# bird_beaks_3_0.net
KiCad netlist of a schematic drawn in EAGLE
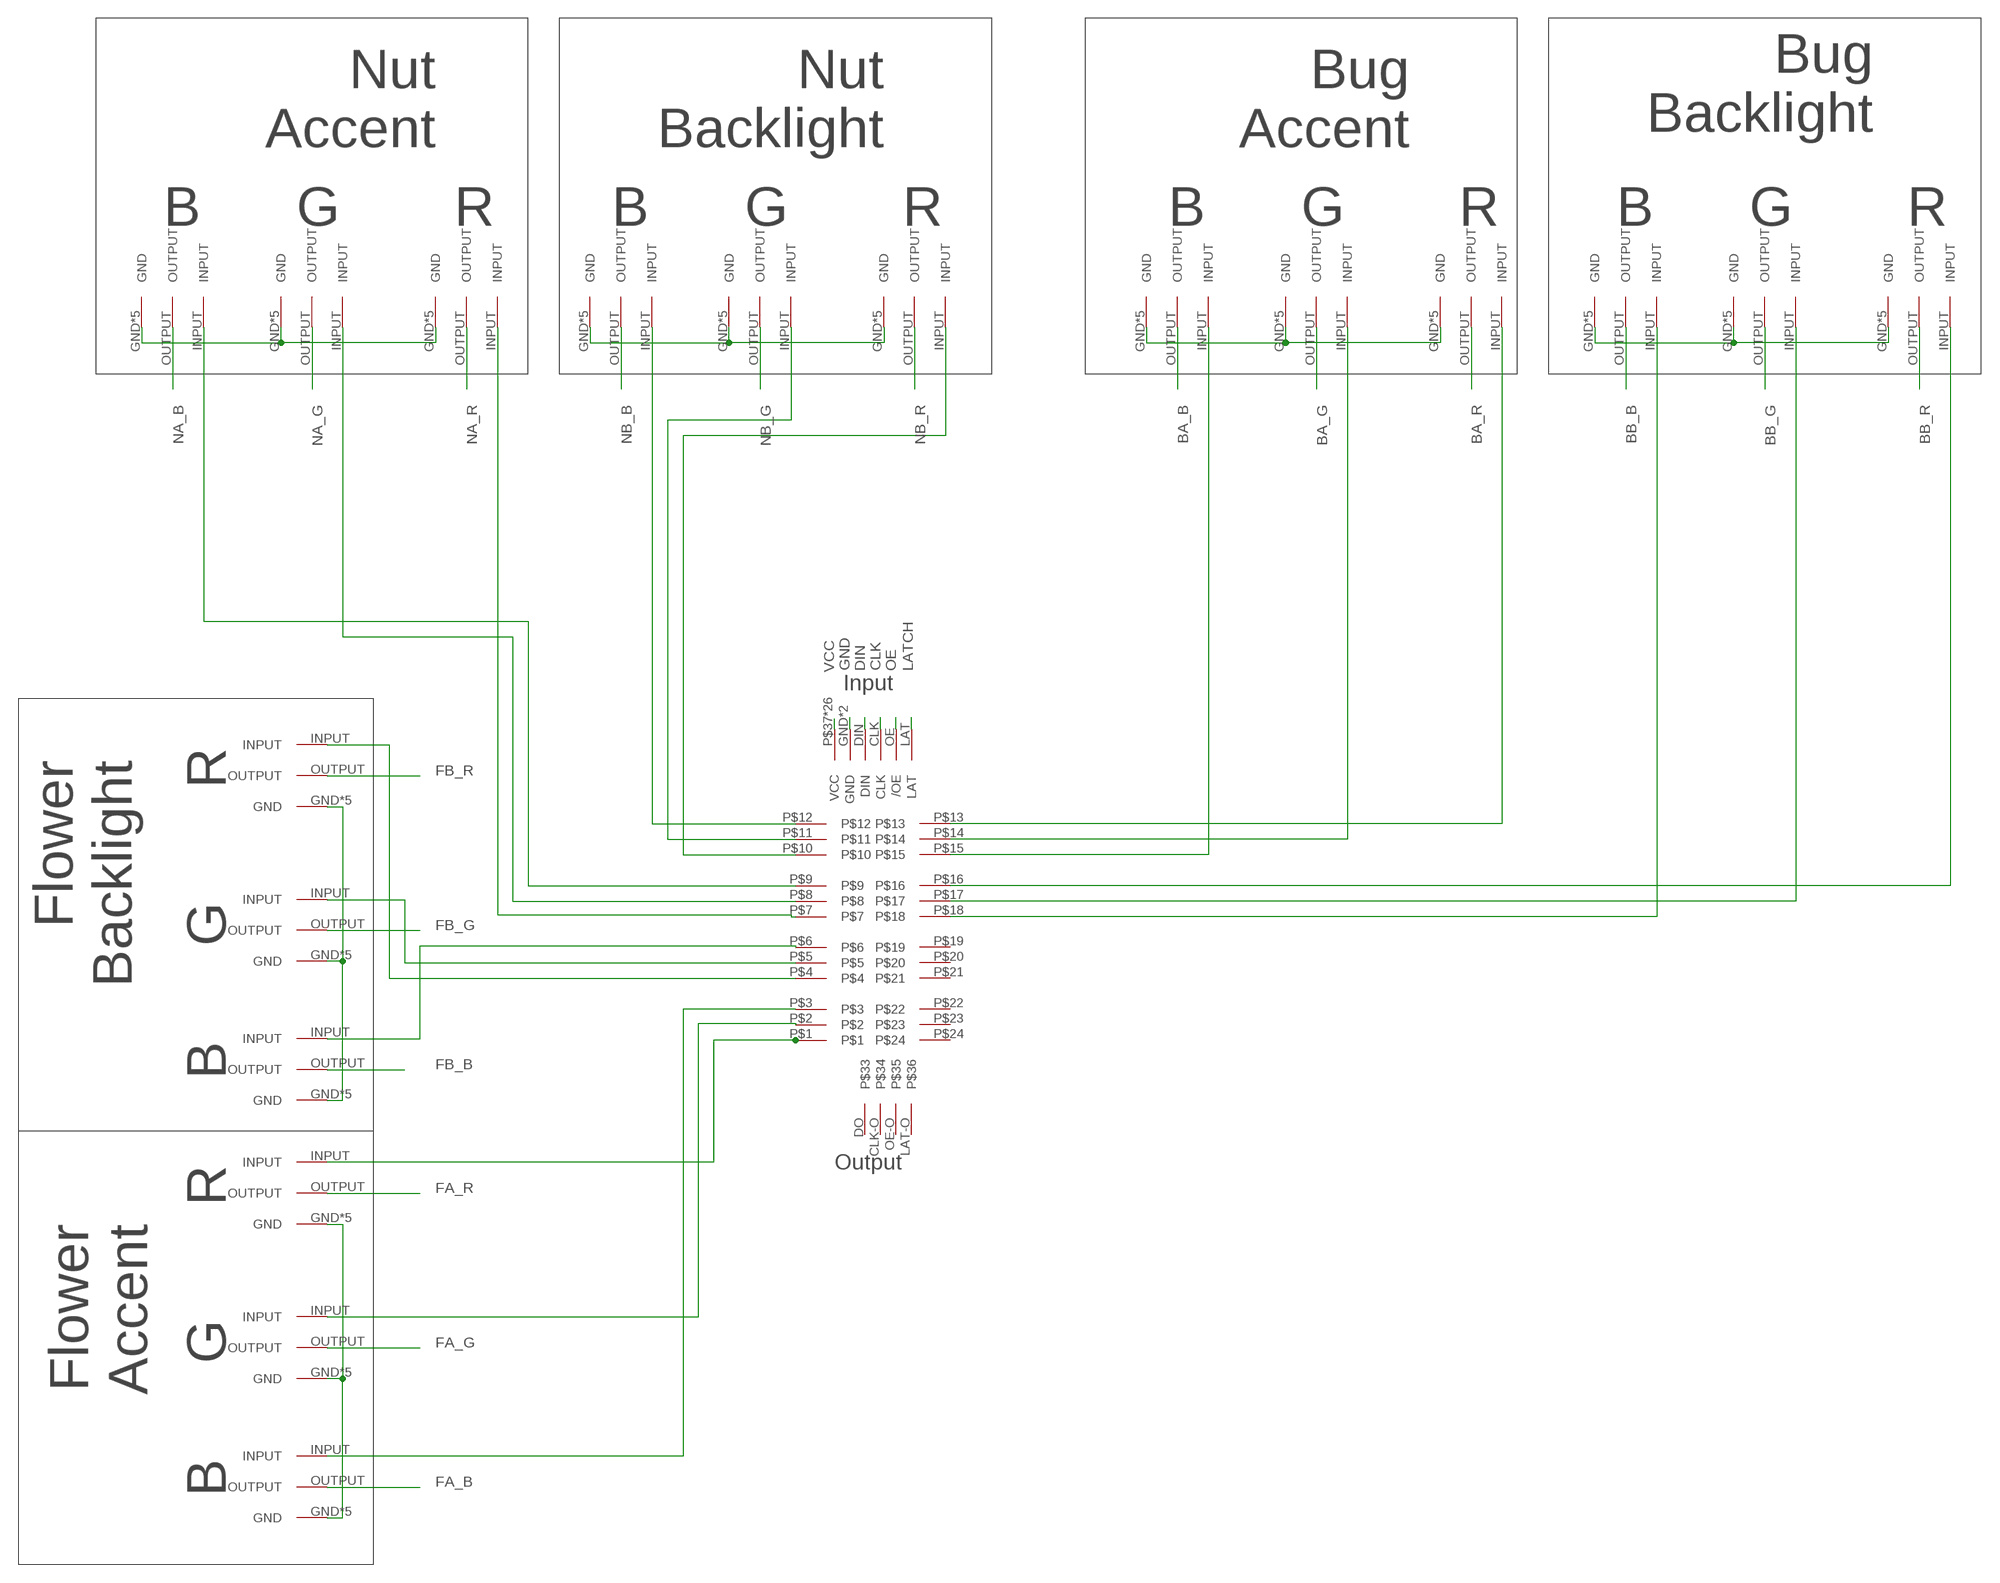
[diagram p0: schematic, sheet 1]
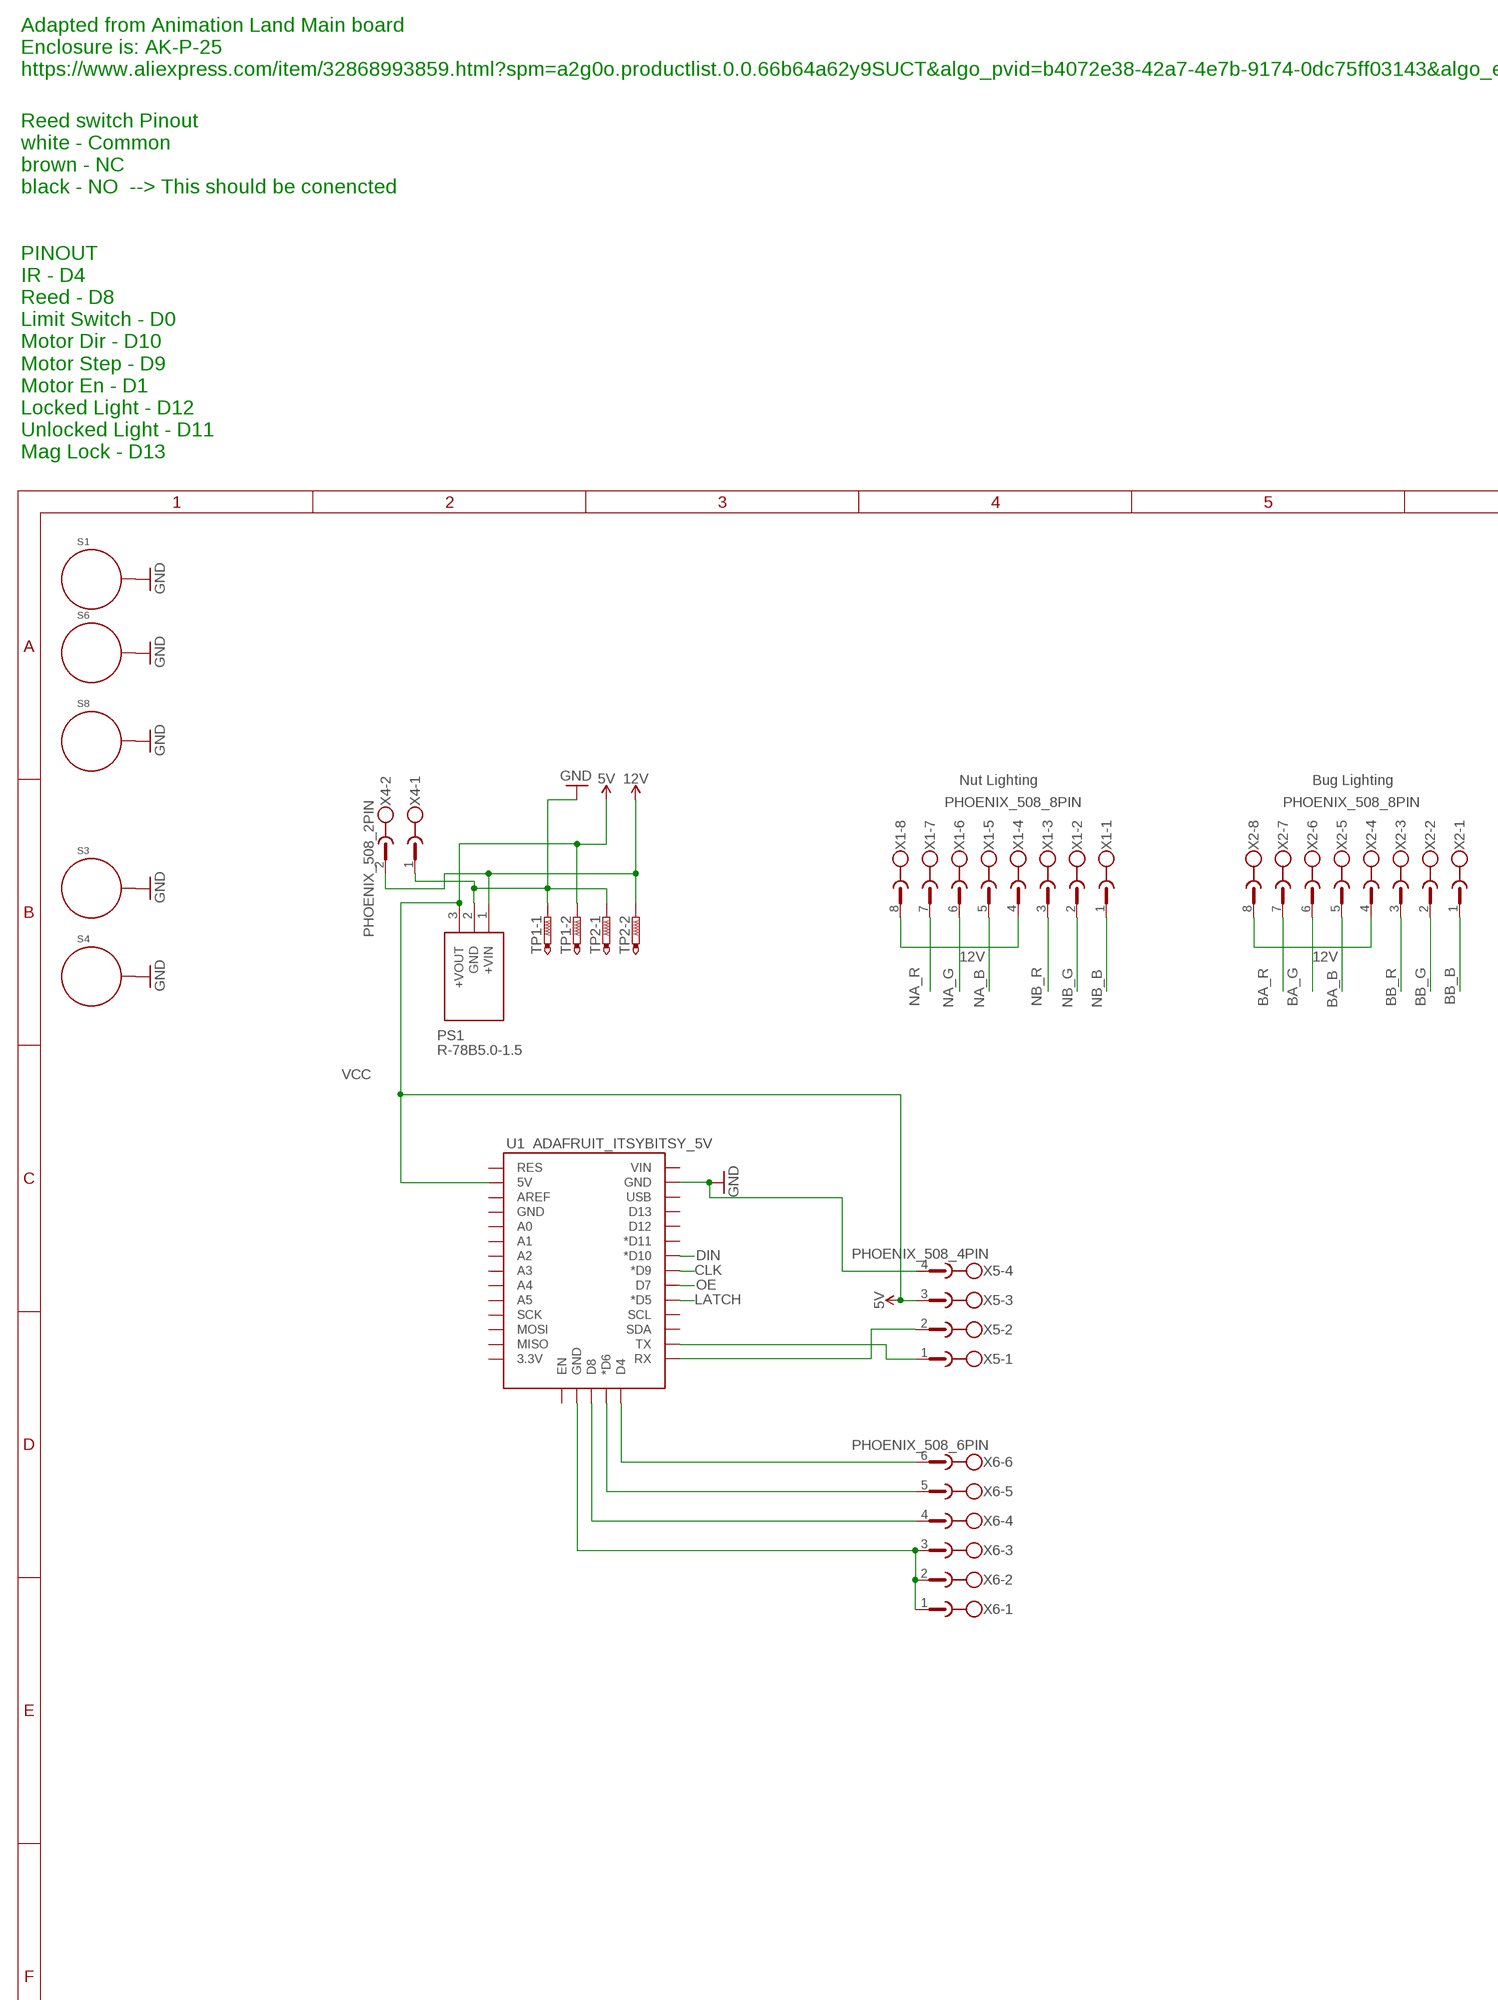
[diagram p1: schematic, sheet 2, part 1 of 2]
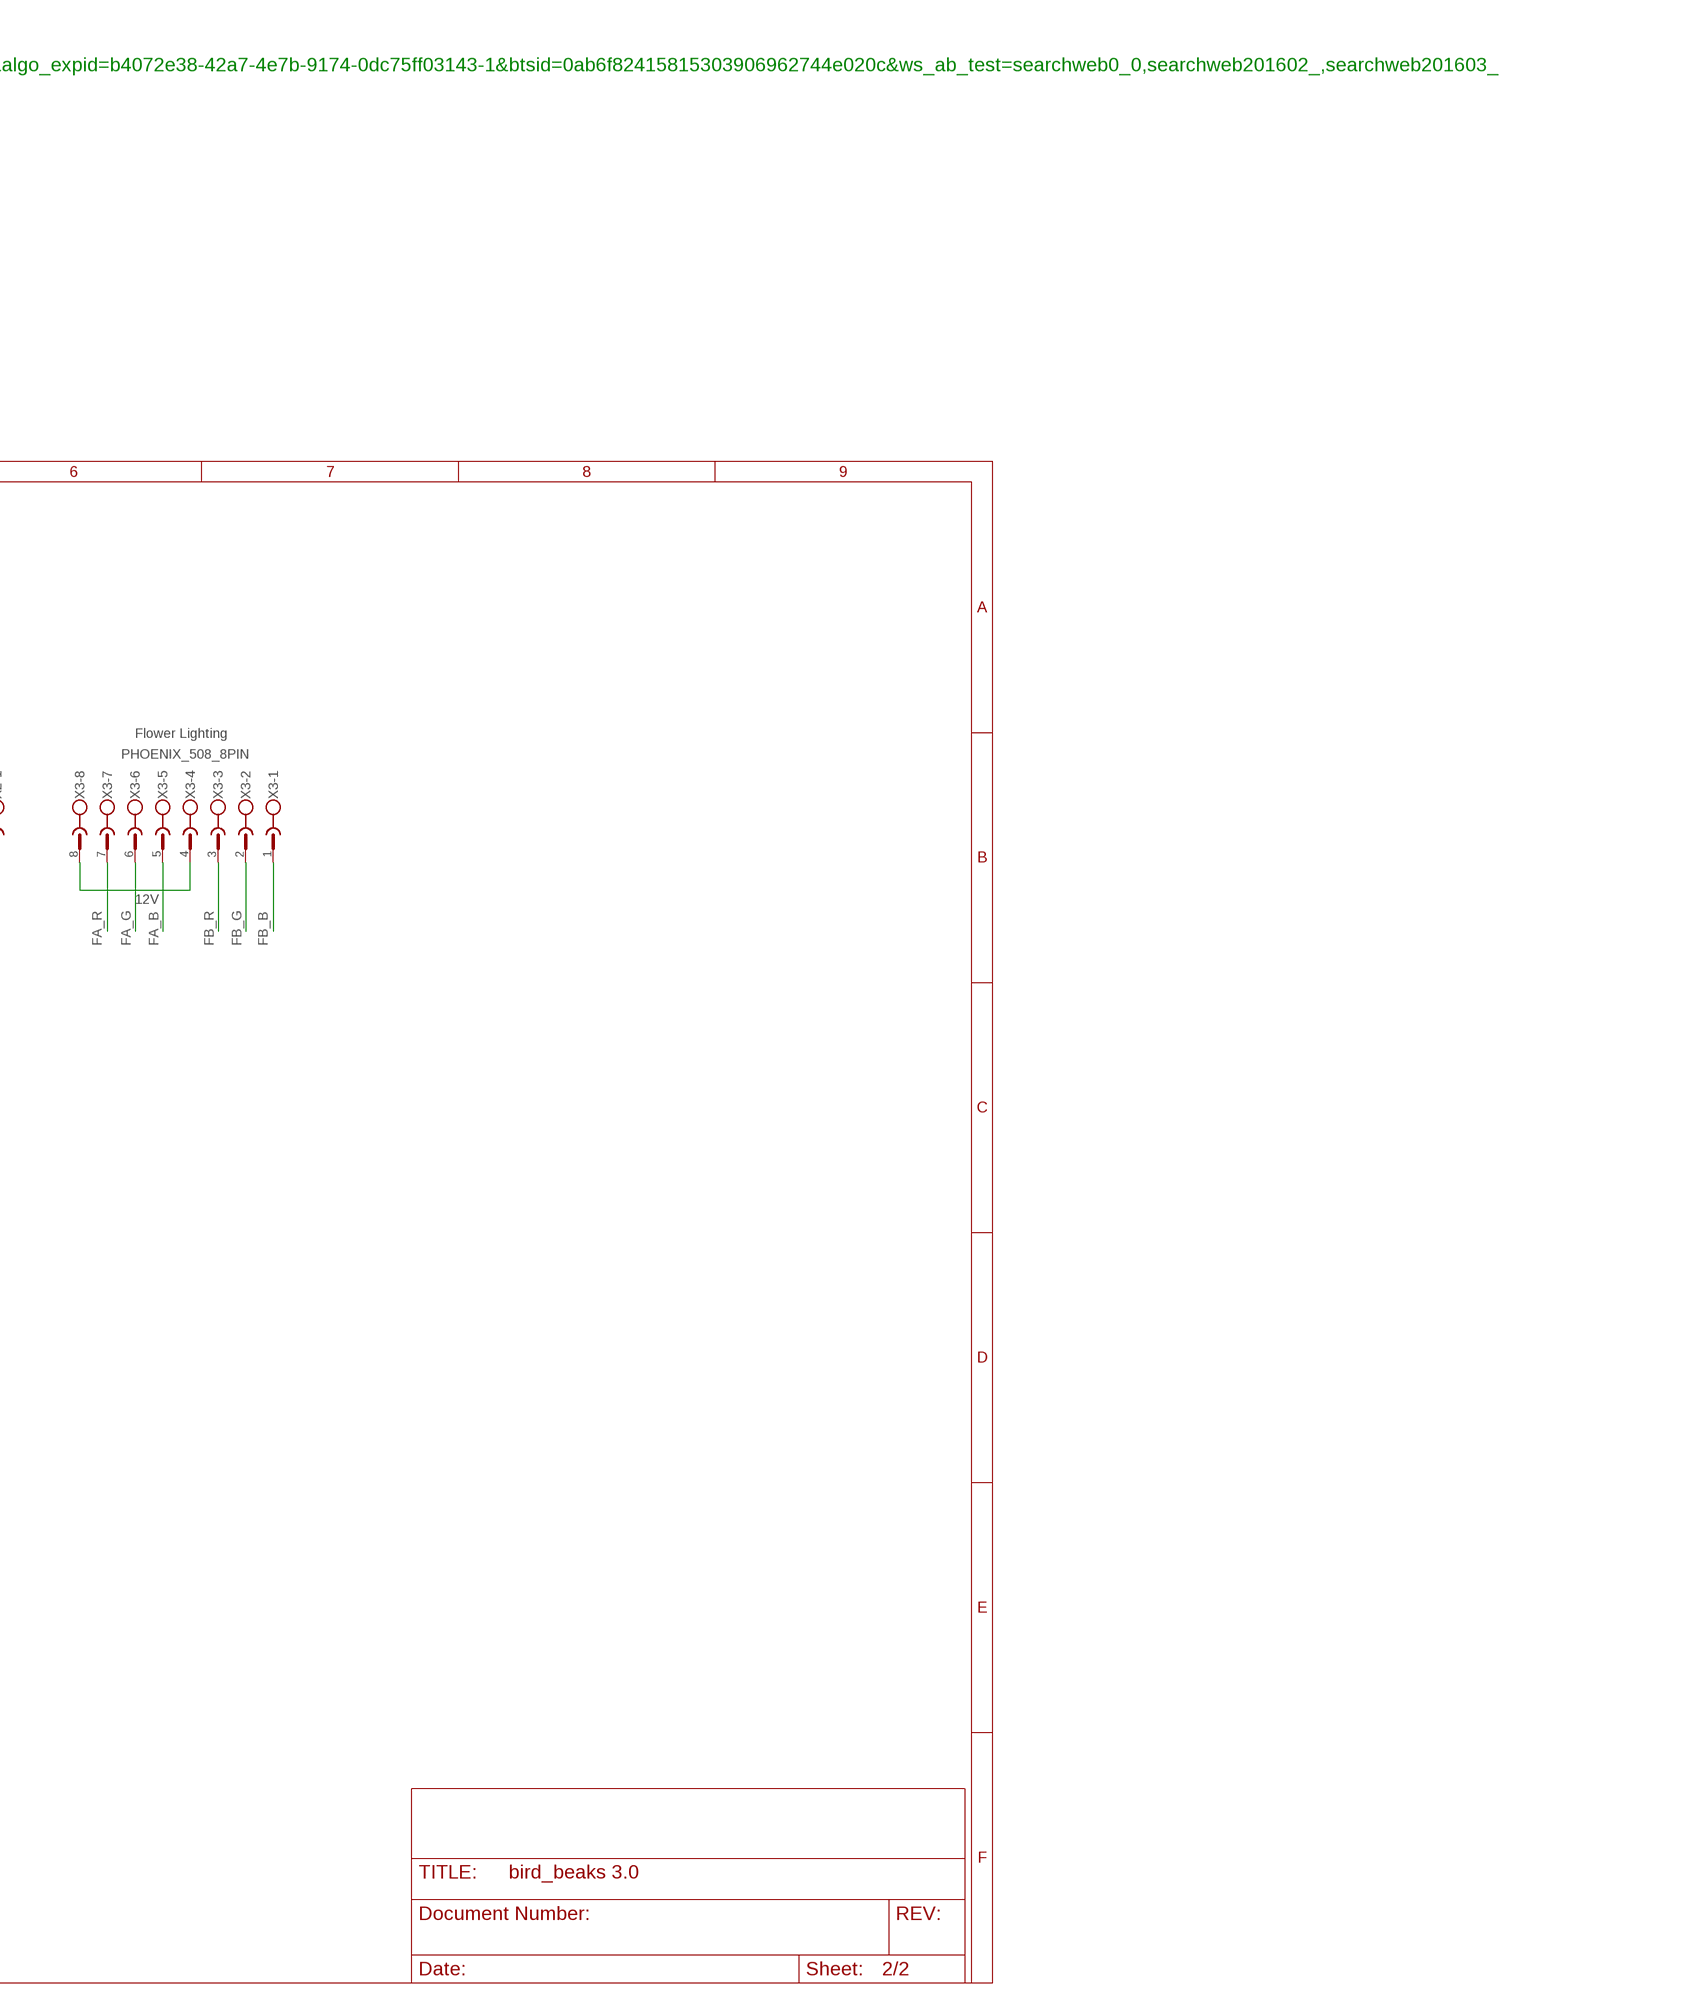
[diagram p2: schematic, sheet 2, part 2 of 2]

(export (version "E")
  (design (tool "Eeschema 10.0.6"))
  (components
    (comp (ref "PS1")
      (value "R-78B5.0-1.5")
      (footprint "eagle-import:R78B5015")
      (fields (field (name "MOUSER_PART_NUMBER") "919-R-78B5.0-1.5"))
      (libsource (lib "eagle-import") (part "R-78B5.0-1.5"))
    )
    (comp (ref "S1")
      (value "STANDOFF_ELECTRICAL5-32")
      (footprint "eagle-import:STANDOFF_ELECTRICAL_5_32")
      (libsource (lib "eagle-import") (part "STANDOFF_ELECTRICAL5-32"))
    )
    (comp (ref "S3")
      (value "STANDOFF_ELECTRICAL5-32")
      (footprint "eagle-import:STANDOFF_ELECTRICAL_5_32")
      (libsource (lib "eagle-import") (part "STANDOFF_ELECTRICAL5-32"))
    )
    (comp (ref "S4")
      (value "STANDOFF_ELECTRICAL5-32")
      (footprint "eagle-import:STANDOFF_ELECTRICAL_5_32")
      (libsource (lib "eagle-import") (part "STANDOFF_ELECTRICAL5-32"))
    )
    (comp (ref "S6")
      (value "STANDOFF_ELECTRICAL5-32")
      (footprint "eagle-import:STANDOFF_ELECTRICAL_5_32")
      (libsource (lib "eagle-import") (part "STANDOFF_ELECTRICAL5-32"))
    )
    (comp (ref "S8")
      (value "STANDOFF_ELECTRICAL5-32")
      (footprint "eagle-import:STANDOFF_ELECTRICAL_5_32")
      (libsource (lib "eagle-import") (part "STANDOFF_ELECTRICAL5-32"))
    )
    (comp (ref "TP1")
      (value "PTR2")
      (footprint "eagle-import:P2-38-17")
      (libsource (lib "eagle-import") (part "PTR2"))
    )
    (comp (ref "TP2")
      (value "PTR2")
      (footprint "eagle-import:P2-38-17")
      (libsource (lib "eagle-import") (part "PTR2"))
    )
    (comp (ref "U1")
      (value "ADAFRUIT_ITSYBITSY_5V")
      (footprint "eagle-import:ADAFRUIT_ITSYBITSY")
      (libsource (lib "eagle-import") (part "ADAFRUIT_ITSYBITSY_5V"))
    )
    (comp (ref "X1")
      (value "PHOENIX_508_8PIN")
      (footprint "eagle-import:PHOENIX_508_8PIN")
      (fields (field (name "MF") "FARNELL") (field (name "MPN") "1757307"))
      (libsource (lib "eagle-import") (part "PHOENIX_508_8PIN"))
    )
    (comp (ref "X2")
      (value "PHOENIX_508_8PIN")
      (footprint "eagle-import:PHOENIX_508_8PIN")
      (fields (field (name "MF") "FARNELL") (field (name "MPN") "1757307"))
      (libsource (lib "eagle-import") (part "PHOENIX_508_8PIN"))
    )
    (comp (ref "X3")
      (value "PHOENIX_508_8PIN")
      (footprint "eagle-import:PHOENIX_508_8PIN")
      (fields (field (name "MF") "FARNELL") (field (name "MPN") "1757307"))
      (libsource (lib "eagle-import") (part "PHOENIX_508_8PIN"))
    )
    (comp (ref "X4")
      (value "PHOENIX_508_2PIN")
      (footprint "eagle-import:PHOENIX_508_2PIN")
      (fields (field (name "MF") "FARNELL") (field (name "MPN") "1757242"))
      (libsource (lib "eagle-import") (part "PHOENIX_508_2PIN"))
    )
    (comp (ref "X5")
      (value "PHOENIX_508_4PIN")
      (footprint "eagle-import:PHOENIX_508_4PIN")
      (fields (field (name "MF") "FARNELL") (field (name "MPN") "1757268"))
      (libsource (lib "eagle-import") (part "PHOENIX_508_4PIN"))
    )
    (comp (ref "X6")
      (value "PHOENIX_508_6PIN")
      (footprint "eagle-import:PHOENIX_508_6PIN")
      (fields (field (name "MF") "FARNELL") (field (name "MPN") "1757284"))
      (libsource (lib "eagle-import") (part "PHOENIX_508_6PIN"))
    )
    (comp (ref "U$1")
      (value "TLC5847")
      (footprint "eagle-import:TLC5947")
      (libsource (lib "eagle-import") (part "TLC5847"))
    )
    (comp (ref "U$2")
      (value "MODULE_MOSFET")
      (footprint "eagle-import:MODULE_MOSFET")
      (libsource (lib "eagle-import") (part "MODULE_MOSFET"))
    )
    (comp (ref "U$3")
      (value "MODULE_MOSFET")
      (footprint "eagle-import:MODULE_MOSFET")
      (libsource (lib "eagle-import") (part "MODULE_MOSFET"))
    )
    (comp (ref "U$4")
      (value "MODULE_MOSFET")
      (footprint "eagle-import:MODULE_MOSFET")
      (libsource (lib "eagle-import") (part "MODULE_MOSFET"))
    )
    (comp (ref "U$5")
      (value "MODULE_MOSFET")
      (footprint "eagle-import:MODULE_MOSFET")
      (libsource (lib "eagle-import") (part "MODULE_MOSFET"))
    )
    (comp (ref "U$6")
      (value "MODULE_MOSFET")
      (footprint "eagle-import:MODULE_MOSFET")
      (libsource (lib "eagle-import") (part "MODULE_MOSFET"))
    )
    (comp (ref "U$7")
      (value "MODULE_MOSFET")
      (footprint "eagle-import:MODULE_MOSFET")
      (libsource (lib "eagle-import") (part "MODULE_MOSFET"))
    )
    (comp (ref "U$8")
      (value "MODULE_MOSFET")
      (footprint "eagle-import:MODULE_MOSFET")
      (libsource (lib "eagle-import") (part "MODULE_MOSFET"))
    )
    (comp (ref "U$9")
      (value "MODULE_MOSFET")
      (footprint "eagle-import:MODULE_MOSFET")
      (libsource (lib "eagle-import") (part "MODULE_MOSFET"))
    )
    (comp (ref "U$10")
      (value "MODULE_MOSFET")
      (footprint "eagle-import:MODULE_MOSFET")
      (libsource (lib "eagle-import") (part "MODULE_MOSFET"))
    )
    (comp (ref "U$11")
      (value "MODULE_MOSFET")
      (footprint "eagle-import:MODULE_MOSFET")
      (libsource (lib "eagle-import") (part "MODULE_MOSFET"))
    )
    (comp (ref "U$12")
      (value "MODULE_MOSFET")
      (footprint "eagle-import:MODULE_MOSFET")
      (libsource (lib "eagle-import") (part "MODULE_MOSFET"))
    )
    (comp (ref "U$13")
      (value "MODULE_MOSFET")
      (footprint "eagle-import:MODULE_MOSFET")
      (libsource (lib "eagle-import") (part "MODULE_MOSFET"))
    )
    (comp (ref "U$14")
      (value "MODULE_MOSFET")
      (footprint "eagle-import:MODULE_MOSFET")
      (libsource (lib "eagle-import") (part "MODULE_MOSFET"))
    )
    (comp (ref "U$15")
      (value "MODULE_MOSFET")
      (footprint "eagle-import:MODULE_MOSFET")
      (libsource (lib "eagle-import") (part "MODULE_MOSFET"))
    )
    (comp (ref "U$16")
      (value "MODULE_MOSFET")
      (footprint "eagle-import:MODULE_MOSFET")
      (libsource (lib "eagle-import") (part "MODULE_MOSFET"))
    )
    (comp (ref "U$17")
      (value "MODULE_MOSFET")
      (footprint "eagle-import:MODULE_MOSFET")
      (libsource (lib "eagle-import") (part "MODULE_MOSFET"))
    )
    (comp (ref "U$18")
      (value "MODULE_MOSFET")
      (footprint "eagle-import:MODULE_MOSFET")
      (libsource (lib "eagle-import") (part "MODULE_MOSFET"))
    )
    (comp (ref "U$19")
      (value "MODULE_MOSFET")
      (footprint "eagle-import:MODULE_MOSFET")
      (libsource (lib "eagle-import") (part "MODULE_MOSFET"))
    )
  )
  (nets
    (net (code "1") (name "12V") (class "Default")
      (node (ref "PS1") (pin "1") (pinfunction "+VIN_1") (pintype "bidirectional"))
      (node (ref "TP2") (pin "TP-2") (pinfunction "TP_TP-2") (pintype "input"))
      (node (ref "X1") (pin "4") (pinfunction "1_4") (pintype "passive"))
      (node (ref "X1") (pin "8") (pinfunction "1_8") (pintype "passive"))
      (node (ref "X2") (pin "4") (pinfunction "1_4") (pintype "passive"))
      (node (ref "X2") (pin "8") (pinfunction "1_8") (pintype "passive"))
      (node (ref "X3") (pin "4") (pinfunction "1_4") (pintype "passive"))
      (node (ref "X3") (pin "8") (pinfunction "1_8") (pintype "passive"))
      (node (ref "X4") (pin "2") (pinfunction "1_2") (pintype "passive"))
    )
    (net (code "2") (name "BA_B") (class "Default")
      (node (ref "U$14") (pin "OUTPUT") (pinfunction "OUTPUT_OUTPUT") (pintype "bidirectional"))
      (node (ref "X2") (pin "5") (pinfunction "1_5") (pintype "passive"))
    )
    (net (code "3") (name "BA_G") (class "Default")
      (node (ref "U$16") (pin "OUTPUT") (pinfunction "OUTPUT_OUTPUT") (pintype "bidirectional"))
      (node (ref "X2") (pin "6") (pinfunction "1_6") (pintype "passive"))
    )
    (net (code "4") (name "BA_R") (class "Default")
      (node (ref "U$15") (pin "OUTPUT") (pinfunction "OUTPUT_OUTPUT") (pintype "bidirectional"))
      (node (ref "X2") (pin "7") (pinfunction "1_7") (pintype "passive"))
    )
    (net (code "5") (name "BB_B") (class "Default")
      (node (ref "U$17") (pin "OUTPUT") (pinfunction "OUTPUT_OUTPUT") (pintype "bidirectional"))
      (node (ref "X2") (pin "1") (pinfunction "1_1") (pintype "passive"))
    )
    (net (code "6") (name "BB_G") (class "Default")
      (node (ref "U$19") (pin "OUTPUT") (pinfunction "OUTPUT_OUTPUT") (pintype "bidirectional"))
      (node (ref "X2") (pin "2") (pinfunction "1_2") (pintype "passive"))
    )
    (net (code "7") (name "BB_R") (class "Default")
      (node (ref "U$18") (pin "OUTPUT") (pinfunction "OUTPUT_OUTPUT") (pintype "bidirectional"))
      (node (ref "X2") (pin "3") (pinfunction "1_3") (pintype "passive"))
    )
    (net (code "8") (name "CLK") (class "Default")
      (node (ref "U$1") (pin "CLK") (pinfunction "CLK_CLK") (pintype "bidirectional"))
      (node (ref "U1") (pin "D9") (pinfunction "*D9_D9") (pintype "bidirectional"))
    )
    (net (code "9") (name "DIN") (class "Default")
      (node (ref "U$1") (pin "DIN") (pinfunction "DIN_DIN") (pintype "bidirectional"))
      (node (ref "U1") (pin "D10") (pinfunction "*D10_D10") (pintype "bidirectional"))
    )
    (net (code "10") (name "FA_B") (class "Default")
      (node (ref "U$5") (pin "OUTPUT") (pinfunction "OUTPUT_OUTPUT") (pintype "bidirectional"))
      (node (ref "X3") (pin "5") (pinfunction "1_5") (pintype "passive"))
    )
    (net (code "11") (name "FA_G") (class "Default")
      (node (ref "U$7") (pin "OUTPUT") (pinfunction "OUTPUT_OUTPUT") (pintype "bidirectional"))
      (node (ref "X3") (pin "6") (pinfunction "1_6") (pintype "passive"))
    )
    (net (code "12") (name "FA_R") (class "Default")
      (node (ref "U$6") (pin "OUTPUT") (pinfunction "OUTPUT_OUTPUT") (pintype "bidirectional"))
      (node (ref "X3") (pin "7") (pinfunction "1_7") (pintype "passive"))
    )
    (net (code "13") (name "FB_B") (class "Default")
      (node (ref "U$2") (pin "OUTPUT") (pinfunction "OUTPUT_OUTPUT") (pintype "bidirectional"))
      (node (ref "X3") (pin "1") (pinfunction "1_1") (pintype "passive"))
    )
    (net (code "14") (name "FB_G") (class "Default")
      (node (ref "U$4") (pin "OUTPUT") (pinfunction "OUTPUT_OUTPUT") (pintype "bidirectional"))
      (node (ref "X3") (pin "2") (pinfunction "1_2") (pintype "passive"))
    )
    (net (code "15") (name "FB_R") (class "Default")
      (node (ref "U$3") (pin "OUTPUT") (pinfunction "OUTPUT_OUTPUT") (pintype "bidirectional"))
      (node (ref "X3") (pin "3") (pinfunction "1_3") (pintype "passive"))
    )
    (net (code "16") (name "GND") (class "Default")
      (node (ref "PS1") (pin "2") (pinfunction "GND_2") (pintype "bidirectional"))
      (node (ref "S1") (pin "P1") (pinfunction "P$1_P1") (pintype "bidirectional"))
      (node (ref "S3") (pin "P1") (pinfunction "P$1_P1") (pintype "bidirectional"))
      (node (ref "S4") (pin "P1") (pinfunction "P$1_P1") (pintype "bidirectional"))
      (node (ref "S6") (pin "P1") (pinfunction "P$1_P1") (pintype "bidirectional"))
      (node (ref "S8") (pin "P1") (pinfunction "P$1_P1") (pintype "bidirectional"))
      (node (ref "TP1") (pin "TP-1") (pinfunction "TP_TP-1") (pintype "input"))
      (node (ref "TP2") (pin "TP-1") (pinfunction "TP_TP-1") (pintype "input"))
      (node (ref "U$1") (pin "GND") (pinfunction "GND_GND") (pintype "bidirectional"))
      (node (ref "U$1") (pin "GND-O") (pinfunction "GND_GND-O") (pintype "bidirectional"))
      (node (ref "U1") (pin "GND@2") (pinfunction "GND_GND@2") (pintype "bidirectional"))
      (node (ref "X4") (pin "1") (pinfunction "1_1") (pintype "passive"))
      (node (ref "X5") (pin "4") (pinfunction "1_4") (pintype "passive"))
    )
    (net (code "17") (name "LATCH") (class "Default")
      (node (ref "U$1") (pin "LAT") (pinfunction "LAT_LAT") (pintype "bidirectional"))
      (node (ref "U1") (pin "D5") (pinfunction "*D5_D5") (pintype "bidirectional"))
    )
    (net (code "18") (name "NA_B") (class "Default")
      (node (ref "U$8") (pin "OUTPUT") (pinfunction "OUTPUT_OUTPUT") (pintype "bidirectional"))
      (node (ref "X1") (pin "5") (pinfunction "1_5") (pintype "passive"))
    )
    (net (code "19") (name "NA_G") (class "Default")
      (node (ref "U$10") (pin "OUTPUT") (pinfunction "OUTPUT_OUTPUT") (pintype "bidirectional"))
      (node (ref "X1") (pin "6") (pinfunction "1_6") (pintype "passive"))
    )
    (net (code "20") (name "NA_R") (class "Default")
      (node (ref "U$9") (pin "OUTPUT") (pinfunction "OUTPUT_OUTPUT") (pintype "bidirectional"))
      (node (ref "X1") (pin "7") (pinfunction "1_7") (pintype "passive"))
    )
    (net (code "21") (name "NB_B") (class "Default")
      (node (ref "U$11") (pin "OUTPUT") (pinfunction "OUTPUT_OUTPUT") (pintype "bidirectional"))
      (node (ref "X1") (pin "1") (pinfunction "1_1") (pintype "passive"))
    )
    (net (code "22") (name "NB_G") (class "Default")
      (node (ref "U$13") (pin "OUTPUT") (pinfunction "OUTPUT_OUTPUT") (pintype "bidirectional"))
      (node (ref "X1") (pin "2") (pinfunction "1_2") (pintype "passive"))
    )
    (net (code "23") (name "NB_R") (class "Default")
      (node (ref "U$12") (pin "OUTPUT") (pinfunction "OUTPUT_OUTPUT") (pintype "bidirectional"))
      (node (ref "X1") (pin "3") (pinfunction "1_3") (pintype "passive"))
    )
    (net (code "24") (name "Net-(U$1-PadP$1)") (class "Default")
      (node (ref "U$1") (pin "P$1") (pinfunction "P$1_P$1") (pintype "bidirectional"))
      (node (ref "U$6") (pin "INPUT") (pinfunction "INPUT_INPUT") (pintype "bidirectional"))
    )
    (net (code "25") (name "Net-(U$1-PadP$2)") (class "Default")
      (node (ref "U$1") (pin "P$2") (pinfunction "P$2_P$2") (pintype "bidirectional"))
      (node (ref "U$7") (pin "INPUT") (pinfunction "INPUT_INPUT") (pintype "bidirectional"))
    )
    (net (code "26") (name "Net-(U$1-PadP$3)") (class "Default")
      (node (ref "U$1") (pin "P$3") (pinfunction "P$3_P$3") (pintype "bidirectional"))
      (node (ref "U$5") (pin "INPUT") (pinfunction "INPUT_INPUT") (pintype "bidirectional"))
    )
    (net (code "27") (name "Net-(U$1-PadP$4)") (class "Default")
      (node (ref "U$1") (pin "P$4") (pinfunction "P$4_P$4") (pintype "bidirectional"))
      (node (ref "U$3") (pin "INPUT") (pinfunction "INPUT_INPUT") (pintype "bidirectional"))
    )
    (net (code "28") (name "Net-(U$1-PadP$5)") (class "Default")
      (node (ref "U$1") (pin "P$5") (pinfunction "P$5_P$5") (pintype "bidirectional"))
      (node (ref "U$4") (pin "INPUT") (pinfunction "INPUT_INPUT") (pintype "bidirectional"))
    )
    (net (code "29") (name "Net-(U$1-PadP$6)") (class "Default")
      (node (ref "U$1") (pin "P$6") (pinfunction "P$6_P$6") (pintype "bidirectional"))
      (node (ref "U$2") (pin "INPUT") (pinfunction "INPUT_INPUT") (pintype "bidirectional"))
    )
    (net (code "30") (name "Net-(U$1-PadP$7)") (class "Default")
      (node (ref "U$1") (pin "P$7") (pinfunction "P$7_P$7") (pintype "bidirectional"))
      (node (ref "U$9") (pin "INPUT") (pinfunction "INPUT_INPUT") (pintype "bidirectional"))
    )
    (net (code "31") (name "Net-(U$1-PadP$8)") (class "Default")
      (node (ref "U$1") (pin "P$8") (pinfunction "P$8_P$8") (pintype "bidirectional"))
      (node (ref "U$10") (pin "INPUT") (pinfunction "INPUT_INPUT") (pintype "bidirectional"))
    )
    (net (code "32") (name "Net-(U$1-PadP$9)") (class "Default")
      (node (ref "U$1") (pin "P$9") (pinfunction "P$9_P$9") (pintype "bidirectional"))
      (node (ref "U$8") (pin "INPUT") (pinfunction "INPUT_INPUT") (pintype "bidirectional"))
    )
    (net (code "33") (name "Net-(U$1-PadP$10)") (class "Default")
      (node (ref "U$1") (pin "P$10") (pinfunction "P$10_P$10") (pintype "bidirectional"))
      (node (ref "U$12") (pin "INPUT") (pinfunction "INPUT_INPUT") (pintype "bidirectional"))
    )
    (net (code "34") (name "Net-(U$1-PadP$11)") (class "Default")
      (node (ref "U$1") (pin "P$11") (pinfunction "P$11_P$11") (pintype "bidirectional"))
      (node (ref "U$13") (pin "INPUT") (pinfunction "INPUT_INPUT") (pintype "bidirectional"))
    )
    (net (code "35") (name "Net-(U$1-PadP$12)") (class "Default")
      (node (ref "U$1") (pin "P$12") (pinfunction "P$12_P$12") (pintype "bidirectional"))
      (node (ref "U$11") (pin "INPUT") (pinfunction "INPUT_INPUT") (pintype "bidirectional"))
    )
    (net (code "36") (name "Net-(U$1-PadP$13)") (class "Default")
      (node (ref "U$1") (pin "P$13") (pinfunction "P$13_P$13") (pintype "bidirectional"))
      (node (ref "U$15") (pin "INPUT") (pinfunction "INPUT_INPUT") (pintype "bidirectional"))
    )
    (net (code "37") (name "Net-(U$1-PadP$14)") (class "Default")
      (node (ref "U$1") (pin "P$14") (pinfunction "P$14_P$14") (pintype "bidirectional"))
      (node (ref "U$16") (pin "INPUT") (pinfunction "INPUT_INPUT") (pintype "bidirectional"))
    )
    (net (code "38") (name "Net-(U$1-PadP$15)") (class "Default")
      (node (ref "U$1") (pin "P$15") (pinfunction "P$15_P$15") (pintype "bidirectional"))
      (node (ref "U$14") (pin "INPUT") (pinfunction "INPUT_INPUT") (pintype "bidirectional"))
    )
    (net (code "39") (name "Net-(U$1-PadP$16)") (class "Default")
      (node (ref "U$1") (pin "P$16") (pinfunction "P$16_P$16") (pintype "bidirectional"))
      (node (ref "U$18") (pin "INPUT") (pinfunction "INPUT_INPUT") (pintype "bidirectional"))
    )
    (net (code "40") (name "Net-(U$1-PadP$17)") (class "Default")
      (node (ref "U$1") (pin "P$17") (pinfunction "P$17_P$17") (pintype "bidirectional"))
      (node (ref "U$19") (pin "INPUT") (pinfunction "INPUT_INPUT") (pintype "bidirectional"))
    )
    (net (code "41") (name "Net-(U$1-PadP$18)") (class "Default")
      (node (ref "U$1") (pin "P$18") (pinfunction "P$18_P$18") (pintype "bidirectional"))
      (node (ref "U$17") (pin "INPUT") (pinfunction "INPUT_INPUT") (pintype "bidirectional"))
    )
    (net (code "42") (name "Net-(U$2-GND-PadGND1)") (class "Default")
      (node (ref "U$2") (pin "GND") (pinfunction "GND_GND") (pintype "bidirectional"))
      (node (ref "U$2") (pin "GND1") (pinfunction "GND_GND1") (pintype "bidirectional"))
      (node (ref "U$2") (pin "GND2") (pinfunction "GND_GND2") (pintype "bidirectional"))
      (node (ref "U$2") (pin "GND3") (pinfunction "GND_GND3") (pintype "bidirectional"))
      (node (ref "U$2") (pin "GND4") (pinfunction "GND_GND4") (pintype "bidirectional"))
      (node (ref "U$3") (pin "GND") (pinfunction "GND_GND") (pintype "bidirectional"))
      (node (ref "U$3") (pin "GND1") (pinfunction "GND_GND1") (pintype "bidirectional"))
      (node (ref "U$3") (pin "GND2") (pinfunction "GND_GND2") (pintype "bidirectional"))
      (node (ref "U$3") (pin "GND3") (pinfunction "GND_GND3") (pintype "bidirectional"))
      (node (ref "U$3") (pin "GND4") (pinfunction "GND_GND4") (pintype "bidirectional"))
      (node (ref "U$4") (pin "GND") (pinfunction "GND_GND") (pintype "bidirectional"))
      (node (ref "U$4") (pin "GND1") (pinfunction "GND_GND1") (pintype "bidirectional"))
      (node (ref "U$4") (pin "GND2") (pinfunction "GND_GND2") (pintype "bidirectional"))
      (node (ref "U$4") (pin "GND3") (pinfunction "GND_GND3") (pintype "bidirectional"))
      (node (ref "U$4") (pin "GND4") (pinfunction "GND_GND4") (pintype "bidirectional"))
    )
    (net (code "43") (name "Net-(U$5-GND-PadGND1)") (class "Default")
      (node (ref "U$5") (pin "GND") (pinfunction "GND_GND") (pintype "bidirectional"))
      (node (ref "U$5") (pin "GND1") (pinfunction "GND_GND1") (pintype "bidirectional"))
      (node (ref "U$5") (pin "GND2") (pinfunction "GND_GND2") (pintype "bidirectional"))
      (node (ref "U$5") (pin "GND3") (pinfunction "GND_GND3") (pintype "bidirectional"))
      (node (ref "U$5") (pin "GND4") (pinfunction "GND_GND4") (pintype "bidirectional"))
      (node (ref "U$6") (pin "GND") (pinfunction "GND_GND") (pintype "bidirectional"))
      (node (ref "U$6") (pin "GND1") (pinfunction "GND_GND1") (pintype "bidirectional"))
      (node (ref "U$6") (pin "GND2") (pinfunction "GND_GND2") (pintype "bidirectional"))
      (node (ref "U$6") (pin "GND3") (pinfunction "GND_GND3") (pintype "bidirectional"))
      (node (ref "U$6") (pin "GND4") (pinfunction "GND_GND4") (pintype "bidirectional"))
      (node (ref "U$7") (pin "GND") (pinfunction "GND_GND") (pintype "bidirectional"))
      (node (ref "U$7") (pin "GND1") (pinfunction "GND_GND1") (pintype "bidirectional"))
      (node (ref "U$7") (pin "GND2") (pinfunction "GND_GND2") (pintype "bidirectional"))
      (node (ref "U$7") (pin "GND3") (pinfunction "GND_GND3") (pintype "bidirectional"))
      (node (ref "U$7") (pin "GND4") (pinfunction "GND_GND4") (pintype "bidirectional"))
    )
    (net (code "44") (name "Net-(U$10-GND-PadGND1)") (class "Default")
      (node (ref "U$10") (pin "GND") (pinfunction "GND_GND") (pintype "bidirectional"))
      (node (ref "U$10") (pin "GND1") (pinfunction "GND_GND1") (pintype "bidirectional"))
      (node (ref "U$10") (pin "GND2") (pinfunction "GND_GND2") (pintype "bidirectional"))
      (node (ref "U$10") (pin "GND3") (pinfunction "GND_GND3") (pintype "bidirectional"))
      (node (ref "U$10") (pin "GND4") (pinfunction "GND_GND4") (pintype "bidirectional"))
      (node (ref "U$8") (pin "GND") (pinfunction "GND_GND") (pintype "bidirectional"))
      (node (ref "U$8") (pin "GND1") (pinfunction "GND_GND1") (pintype "bidirectional"))
      (node (ref "U$8") (pin "GND2") (pinfunction "GND_GND2") (pintype "bidirectional"))
      (node (ref "U$8") (pin "GND3") (pinfunction "GND_GND3") (pintype "bidirectional"))
      (node (ref "U$8") (pin "GND4") (pinfunction "GND_GND4") (pintype "bidirectional"))
      (node (ref "U$9") (pin "GND") (pinfunction "GND_GND") (pintype "bidirectional"))
      (node (ref "U$9") (pin "GND1") (pinfunction "GND_GND1") (pintype "bidirectional"))
      (node (ref "U$9") (pin "GND2") (pinfunction "GND_GND2") (pintype "bidirectional"))
      (node (ref "U$9") (pin "GND3") (pinfunction "GND_GND3") (pintype "bidirectional"))
      (node (ref "U$9") (pin "GND4") (pinfunction "GND_GND4") (pintype "bidirectional"))
    )
    (net (code "45") (name "Net-(U$11-GND-PadGND1)") (class "Default")
      (node (ref "U$11") (pin "GND") (pinfunction "GND_GND") (pintype "bidirectional"))
      (node (ref "U$11") (pin "GND1") (pinfunction "GND_GND1") (pintype "bidirectional"))
      (node (ref "U$11") (pin "GND2") (pinfunction "GND_GND2") (pintype "bidirectional"))
      (node (ref "U$11") (pin "GND3") (pinfunction "GND_GND3") (pintype "bidirectional"))
      (node (ref "U$11") (pin "GND4") (pinfunction "GND_GND4") (pintype "bidirectional"))
      (node (ref "U$12") (pin "GND") (pinfunction "GND_GND") (pintype "bidirectional"))
      (node (ref "U$12") (pin "GND1") (pinfunction "GND_GND1") (pintype "bidirectional"))
      (node (ref "U$12") (pin "GND2") (pinfunction "GND_GND2") (pintype "bidirectional"))
      (node (ref "U$12") (pin "GND3") (pinfunction "GND_GND3") (pintype "bidirectional"))
      (node (ref "U$12") (pin "GND4") (pinfunction "GND_GND4") (pintype "bidirectional"))
      (node (ref "U$13") (pin "GND") (pinfunction "GND_GND") (pintype "bidirectional"))
      (node (ref "U$13") (pin "GND1") (pinfunction "GND_GND1") (pintype "bidirectional"))
      (node (ref "U$13") (pin "GND2") (pinfunction "GND_GND2") (pintype "bidirectional"))
      (node (ref "U$13") (pin "GND3") (pinfunction "GND_GND3") (pintype "bidirectional"))
      (node (ref "U$13") (pin "GND4") (pinfunction "GND_GND4") (pintype "bidirectional"))
    )
    (net (code "46") (name "Net-(U$14-GND-PadGND1)") (class "Default")
      (node (ref "U$14") (pin "GND") (pinfunction "GND_GND") (pintype "bidirectional"))
      (node (ref "U$14") (pin "GND1") (pinfunction "GND_GND1") (pintype "bidirectional"))
      (node (ref "U$14") (pin "GND2") (pinfunction "GND_GND2") (pintype "bidirectional"))
      (node (ref "U$14") (pin "GND3") (pinfunction "GND_GND3") (pintype "bidirectional"))
      (node (ref "U$14") (pin "GND4") (pinfunction "GND_GND4") (pintype "bidirectional"))
      (node (ref "U$15") (pin "GND") (pinfunction "GND_GND") (pintype "bidirectional"))
      (node (ref "U$15") (pin "GND1") (pinfunction "GND_GND1") (pintype "bidirectional"))
      (node (ref "U$15") (pin "GND2") (pinfunction "GND_GND2") (pintype "bidirectional"))
      (node (ref "U$15") (pin "GND3") (pinfunction "GND_GND3") (pintype "bidirectional"))
      (node (ref "U$15") (pin "GND4") (pinfunction "GND_GND4") (pintype "bidirectional"))
      (node (ref "U$16") (pin "GND") (pinfunction "GND_GND") (pintype "bidirectional"))
      (node (ref "U$16") (pin "GND1") (pinfunction "GND_GND1") (pintype "bidirectional"))
      (node (ref "U$16") (pin "GND2") (pinfunction "GND_GND2") (pintype "bidirectional"))
      (node (ref "U$16") (pin "GND3") (pinfunction "GND_GND3") (pintype "bidirectional"))
      (node (ref "U$16") (pin "GND4") (pinfunction "GND_GND4") (pintype "bidirectional"))
    )
    (net (code "47") (name "Net-(U$17-GND-PadGND1)") (class "Default")
      (node (ref "U$17") (pin "GND") (pinfunction "GND_GND") (pintype "bidirectional"))
      (node (ref "U$17") (pin "GND1") (pinfunction "GND_GND1") (pintype "bidirectional"))
      (node (ref "U$17") (pin "GND2") (pinfunction "GND_GND2") (pintype "bidirectional"))
      (node (ref "U$17") (pin "GND3") (pinfunction "GND_GND3") (pintype "bidirectional"))
      (node (ref "U$17") (pin "GND4") (pinfunction "GND_GND4") (pintype "bidirectional"))
      (node (ref "U$18") (pin "GND") (pinfunction "GND_GND") (pintype "bidirectional"))
      (node (ref "U$18") (pin "GND1") (pinfunction "GND_GND1") (pintype "bidirectional"))
      (node (ref "U$18") (pin "GND2") (pinfunction "GND_GND2") (pintype "bidirectional"))
      (node (ref "U$18") (pin "GND3") (pinfunction "GND_GND3") (pintype "bidirectional"))
      (node (ref "U$18") (pin "GND4") (pinfunction "GND_GND4") (pintype "bidirectional"))
      (node (ref "U$19") (pin "GND") (pinfunction "GND_GND") (pintype "bidirectional"))
      (node (ref "U$19") (pin "GND1") (pinfunction "GND_GND1") (pintype "bidirectional"))
      (node (ref "U$19") (pin "GND2") (pinfunction "GND_GND2") (pintype "bidirectional"))
      (node (ref "U$19") (pin "GND3") (pinfunction "GND_GND3") (pintype "bidirectional"))
      (node (ref "U$19") (pin "GND4") (pinfunction "GND_GND4") (pintype "bidirectional"))
    )
    (net (code "48") (name "Net-(U1-*D6)") (class "Default")
      (node (ref "U1") (pin "D6") (pinfunction "*D6_D6") (pintype "bidirectional"))
      (node (ref "X6") (pin "5") (pinfunction "1_5") (pintype "passive"))
    )
    (net (code "49") (name "Net-(U1-PadTX)") (class "Default")
      (node (ref "U1") (pin "TX") (pinfunction "TX_TX") (pintype "bidirectional"))
      (node (ref "X5") (pin "1") (pinfunction "1_1") (pintype "passive"))
    )
    (net (code "50") (name "Net-(X5B-1)") (class "Default")
      (node (ref "U1") (pin "RX") (pinfunction "RX_RX") (pintype "bidirectional"))
      (node (ref "X5") (pin "2") (pinfunction "1_2") (pintype "passive"))
    )
    (net (code "51") (name "Net-(X6B-1)") (class "Default")
      (node (ref "U1") (pin "GND@1") (pinfunction "GND_GND@1") (pintype "bidirectional"))
      (node (ref "X6") (pin "1") (pinfunction "1_1") (pintype "passive"))
      (node (ref "X6") (pin "2") (pinfunction "1_2") (pintype "passive"))
      (node (ref "X6") (pin "3") (pinfunction "1_3") (pintype "passive"))
    )
    (net (code "52") (name "Net-(X6D-1)") (class "Default")
      (node (ref "U1") (pin "D8") (pinfunction "D8_D8") (pintype "bidirectional"))
      (node (ref "X6") (pin "4") (pinfunction "1_4") (pintype "passive"))
    )
    (net (code "53") (name "Net-(X6F-1)") (class "Default")
      (node (ref "U1") (pin "D4") (pinfunction "D4_D4") (pintype "bidirectional"))
      (node (ref "X6") (pin "6") (pinfunction "1_6") (pintype "passive"))
    )
    (net (code "54") (name "OE") (class "Default")
      (node (ref "U$1") (pin "OE") (pinfunction "/OE_OE") (pintype "bidirectional"))
      (node (ref "U1") (pin "D7") (pinfunction "D7_D7") (pintype "bidirectional"))
    )
    (net (code "55") (name "VCC") (class "Default")
      (node (ref "PS1") (pin "3") (pinfunction "+VOUT_3") (pintype "bidirectional"))
      (node (ref "TP1") (pin "TP-2") (pinfunction "TP_TP-2") (pintype "input"))
      (node (ref "U$1") (pin "P$37") (pinfunction "VCC_P$37") (pintype "bidirectional"))
      (node (ref "U$1") (pin "P$38") (pinfunction "VCC_P$38") (pintype "bidirectional"))
      (node (ref "U$1") (pin "P$39") (pinfunction "VCC_P$39") (pintype "bidirectional"))
      (node (ref "U$1") (pin "P$40") (pinfunction "VCC_P$40") (pintype "bidirectional"))
      (node (ref "U$1") (pin "P$41") (pinfunction "VCC_P$41") (pintype "bidirectional"))
      (node (ref "U$1") (pin "P$42") (pinfunction "VCC_P$42") (pintype "bidirectional"))
      (node (ref "U$1") (pin "P$43") (pinfunction "VCC_P$43") (pintype "bidirectional"))
      (node (ref "U$1") (pin "P$44") (pinfunction "VCC_P$44") (pintype "bidirectional"))
      (node (ref "U$1") (pin "P$45") (pinfunction "VCC_P$45") (pintype "bidirectional"))
      (node (ref "U$1") (pin "P$46") (pinfunction "VCC_P$46") (pintype "bidirectional"))
      (node (ref "U$1") (pin "P$47") (pinfunction "VCC_P$47") (pintype "bidirectional"))
      (node (ref "U$1") (pin "P$48") (pinfunction "VCC_P$48") (pintype "bidirectional"))
      (node (ref "U$1") (pin "P$49") (pinfunction "VCC_P$49") (pintype "bidirectional"))
      (node (ref "U$1") (pin "P$50") (pinfunction "VCC_P$50") (pintype "bidirectional"))
      (node (ref "U$1") (pin "P$51") (pinfunction "VCC_P$51") (pintype "bidirectional"))
      (node (ref "U$1") (pin "P$52") (pinfunction "VCC_P$52") (pintype "bidirectional"))
      (node (ref "U$1") (pin "P$53") (pinfunction "VCC_P$53") (pintype "bidirectional"))
      (node (ref "U$1") (pin "P$54") (pinfunction "VCC_P$54") (pintype "bidirectional"))
      (node (ref "U$1") (pin "P$55") (pinfunction "VCC_P$55") (pintype "bidirectional"))
      (node (ref "U$1") (pin "P$56") (pinfunction "VCC_P$56") (pintype "bidirectional"))
      (node (ref "U$1") (pin "P$57") (pinfunction "VCC_P$57") (pintype "bidirectional"))
      (node (ref "U$1") (pin "P$58") (pinfunction "VCC_P$58") (pintype "bidirectional"))
      (node (ref "U$1") (pin "P$59") (pinfunction "VCC_P$59") (pintype "bidirectional"))
      (node (ref "U$1") (pin "P$60") (pinfunction "VCC_P$60") (pintype "bidirectional"))
      (node (ref "U$1") (pin "VCC") (pinfunction "VCC_VCC") (pintype "bidirectional"))
      (node (ref "U$1") (pin "VCC-O") (pinfunction "VCC_VCC-O") (pintype "bidirectional"))
      (node (ref "U1") (pin "5V") (pinfunction "5V_5V") (pintype "bidirectional"))
      (node (ref "X5") (pin "3") (pinfunction "1_3") (pintype "passive"))
    )
    (net (code "56") (name "unconnected-(U$1-P$33-PadDO)") (class "Default")
      (node (ref "U$1") (pin "DO") (pinfunction "P$33_DO") (pintype "bidirectional"))
    )
    (net (code "57") (name "unconnected-(U$1-P$34-PadCLK-O)") (class "Default")
      (node (ref "U$1") (pin "CLK-O") (pinfunction "P$34_CLK-O") (pintype "bidirectional"))
    )
    (net (code "58") (name "unconnected-(U$1-P$35-PadOE-O)") (class "Default")
      (node (ref "U$1") (pin "OE-O") (pinfunction "P$35_OE-O") (pintype "bidirectional"))
    )
    (net (code "59") (name "unconnected-(U$1-P$36-PadLAT-O)") (class "Default")
      (node (ref "U$1") (pin "LAT-O") (pinfunction "P$36_LAT-O") (pintype "bidirectional"))
    )
    (net (code "60") (name "unconnected-(U$1-PadP$19)") (class "Default")
      (node (ref "U$1") (pin "P$19") (pinfunction "P$19_P$19") (pintype "bidirectional"))
    )
    (net (code "61") (name "unconnected-(U$1-PadP$20)") (class "Default")
      (node (ref "U$1") (pin "P$20") (pinfunction "P$20_P$20") (pintype "bidirectional"))
    )
    (net (code "62") (name "unconnected-(U$1-PadP$21)") (class "Default")
      (node (ref "U$1") (pin "P$21") (pinfunction "P$21_P$21") (pintype "bidirectional"))
    )
    (net (code "63") (name "unconnected-(U$1-PadP$22)") (class "Default")
      (node (ref "U$1") (pin "P$22") (pinfunction "P$22_P$22") (pintype "bidirectional"))
    )
    (net (code "64") (name "unconnected-(U$1-PadP$23)") (class "Default")
      (node (ref "U$1") (pin "P$23") (pinfunction "P$23_P$23") (pintype "bidirectional"))
    )
    (net (code "65") (name "unconnected-(U$1-PadP$24)") (class "Default")
      (node (ref "U$1") (pin "P$24") (pinfunction "P$24_P$24") (pintype "bidirectional"))
    )
    (net (code "66") (name "unconnected-(U1-*D11-PadD11)") (class "Default")
      (node (ref "U1") (pin "D11") (pinfunction "*D11_D11") (pintype "bidirectional"))
    )
    (net (code "67") (name "unconnected-(U1-3.3V-Pad3V)") (class "Default")
      (node (ref "U1") (pin "3V") (pinfunction "3.3V_3V") (pintype "bidirectional"))
    )
    (net (code "68") (name "unconnected-(U1-GND-PadGND@0)") (class "Default")
      (node (ref "U1") (pin "GND@0") (pinfunction "GND_GND@0") (pintype "bidirectional"))
    )
    (net (code "69") (name "unconnected-(U1-PadA0)") (class "Default")
      (node (ref "U1") (pin "A0") (pinfunction "A0_A0") (pintype "bidirectional"))
    )
    (net (code "70") (name "unconnected-(U1-PadA1)") (class "Default")
      (node (ref "U1") (pin "A1") (pinfunction "A1_A1") (pintype "bidirectional"))
    )
    (net (code "71") (name "unconnected-(U1-PadA2)") (class "Default")
      (node (ref "U1") (pin "A2") (pinfunction "A2_A2") (pintype "bidirectional"))
    )
    (net (code "72") (name "unconnected-(U1-PadA3)") (class "Default")
      (node (ref "U1") (pin "A3") (pinfunction "A3_A3") (pintype "bidirectional"))
    )
    (net (code "73") (name "unconnected-(U1-PadA4)") (class "Default")
      (node (ref "U1") (pin "A4") (pinfunction "A4_A4") (pintype "bidirectional"))
    )
    (net (code "74") (name "unconnected-(U1-PadA5)") (class "Default")
      (node (ref "U1") (pin "A5") (pinfunction "A5_A5") (pintype "bidirectional"))
    )
    (net (code "75") (name "unconnected-(U1-PadAREF)") (class "Default")
      (node (ref "U1") (pin "AREF") (pinfunction "AREF_AREF") (pintype "bidirectional"))
    )
    (net (code "76") (name "unconnected-(U1-PadD12)") (class "Default")
      (node (ref "U1") (pin "D12") (pinfunction "D12_D12") (pintype "bidirectional"))
    )
    (net (code "77") (name "unconnected-(U1-PadD13)") (class "Default")
      (node (ref "U1") (pin "D13") (pinfunction "D13_D13") (pintype "bidirectional"))
    )
    (net (code "78") (name "unconnected-(U1-PadEN)") (class "Default")
      (node (ref "U1") (pin "EN") (pinfunction "EN_EN") (pintype "bidirectional"))
    )
    (net (code "79") (name "unconnected-(U1-PadMISO)") (class "Default")
      (node (ref "U1") (pin "MISO") (pinfunction "MISO_MISO") (pintype "bidirectional"))
    )
    (net (code "80") (name "unconnected-(U1-PadMOSI)") (class "Default")
      (node (ref "U1") (pin "MOSI") (pinfunction "MOSI_MOSI") (pintype "bidirectional"))
    )
    (net (code "81") (name "unconnected-(U1-PadRES)") (class "Default")
      (node (ref "U1") (pin "RES") (pinfunction "RES_RES") (pintype "bidirectional"))
    )
    (net (code "82") (name "unconnected-(U1-PadSCK)") (class "Default")
      (node (ref "U1") (pin "SCK") (pinfunction "SCK_SCK") (pintype "bidirectional"))
    )
    (net (code "83") (name "unconnected-(U1-PadSCL)") (class "Default")
      (node (ref "U1") (pin "SCL") (pinfunction "SCL_SCL") (pintype "bidirectional"))
    )
    (net (code "84") (name "unconnected-(U1-PadSDA)") (class "Default")
      (node (ref "U1") (pin "SDA") (pinfunction "SDA_SDA") (pintype "bidirectional"))
    )
    (net (code "85") (name "unconnected-(U1-PadUSB)") (class "Default")
      (node (ref "U1") (pin "USB") (pinfunction "USB_USB") (pintype "bidirectional"))
    )
    (net (code "86") (name "unconnected-(U1-PadVIN)") (class "Default")
      (node (ref "U1") (pin "VIN") (pinfunction "VIN_VIN") (pintype "bidirectional"))
    )
  )
)
